# Micro.net
KiCad netlist of a schematic drawn in Altium Designer
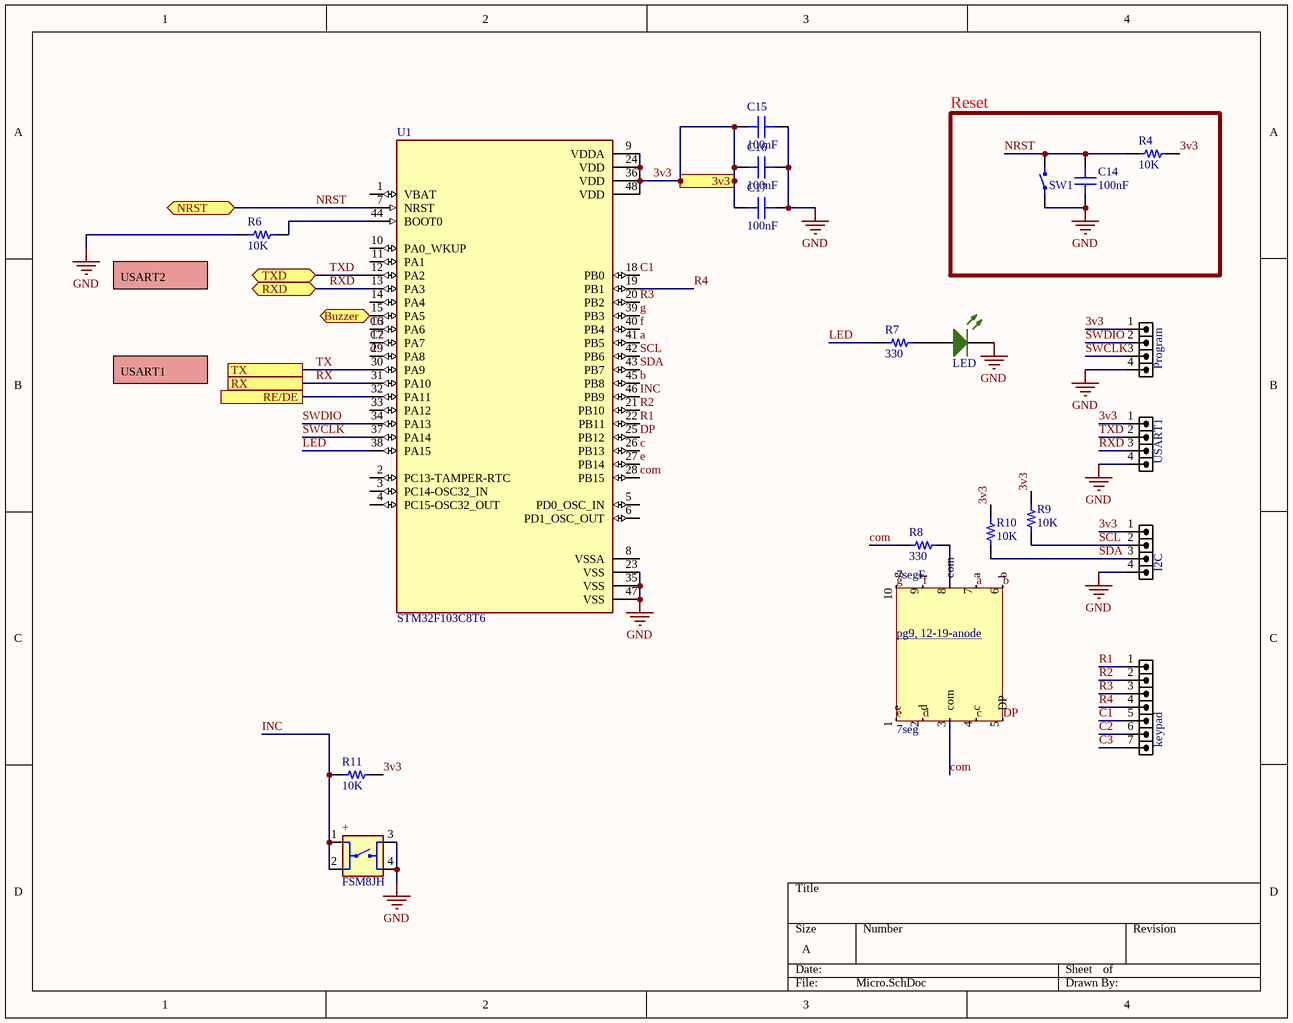
[diagram p0: Micro.SchDoc]

(export (version "E")
  (design (tool "Eeschema 10.0.6"))
  (components
    (comp (ref "+")
      (value "FSM8JH")
      (footprint "SW_FSM8JH")
      (description "Tactile Switch SPST-NO Top Actuated Through Hole")
      (fields (field (name "MF") "TE Connectivity"))
      (libsource (lib "FSM8JH") (part "FSM8JH"))
    )
    (comp (ref "7seg")
      (value "7seg")
      (footprint "PCBComponent_1")
      (description "file:///C:/Users/Tamana/Downloads/7SEG-12-19mm-GREEN-ANOD.pdf")
      (libsource (lib "7seg") (part "7seg"))
    )
    (comp (ref "C14")
      (value "100nF")
      (footprint "CAP 0805_2012")
      (description "SMT Capacitor")
      (libsource (lib "Capacitor") (part "Cap 0805"))
    )
    (comp (ref "C15")
      (value "100nF")
      (footprint "CAP 0805_2012")
      (description "SMT Capacitor")
      (libsource (lib "Capacitor") (part "Cap 0805"))
    )
    (comp (ref "C16")
      (value "100nF")
      (footprint "CAP 0805_2012")
      (description "SMT Capacitor")
      (libsource (lib "Capacitor") (part "Cap 0805"))
    )
    (comp (ref "C17")
      (value "100nF")
      (footprint "CAP 0805_2012")
      (description "SMT Capacitor")
      (libsource (lib "Capacitor") (part "Cap 0805"))
    )
    (comp (ref "I2C")
      (value "HDR1X4")
      (footprint "HDR_1X4")
      (description "CONN, HEADER, Male, pitch: 2.54mm, 4POS")
      (libsource (lib "Conn Header") (part "HDR_1X4"))
    )
    (comp (ref "keypad")
      (value "HDR1X7")
      (footprint "HDR_1X7")
      (description "CONN, HEADER, Male, pitch: 2.54mm, 7POS")
      (libsource (lib "Conn Header") (part "HDR_1X7"))
    )
    (comp (ref "LED")
      (value "LED SMD 0805 GREEN")
      (footprint "LED_0805_GREEN")
      (libsource (lib "Led") (part "LED SMD 0805 GREEN"))
    )
    (comp (ref "Program")
      (value "HDR1X4")
      (footprint "HDR_1X4")
      (description "CONN, HEADER, Male, pitch: 2.54mm, 4POS")
      (libsource (lib "Conn Header") (part "HDR_1X4"))
    )
    (comp (ref "R4")
      (value "10K")
      (footprint "RES 0805_2012")
      (description "SMT Resistor")
      (libsource (lib "Resistor") (part "Res 0805"))
    )
    (comp (ref "R6")
      (value "10K")
      (footprint "RES 0805_2012")
      (description "SMT Resistor")
      (libsource (lib "Resistor") (part "Res 0805"))
    )
    (comp (ref "R7")
      (value "330")
      (footprint "RES 0805_2012")
      (description "SMT Resistor")
      (libsource (lib "Resistor") (part "Res 0805"))
    )
    (comp (ref "R8")
      (value "330")
      (footprint "RES 0805_2012")
      (description "SMT Resistor")
      (libsource (lib "Resistor") (part "Res 0805"))
    )
    (comp (ref "R9")
      (value "10K")
      (footprint "RES 0805_2012")
      (description "SMT Resistor")
      (libsource (lib "Resistor") (part "Res 0805"))
    )
    (comp (ref "R10")
      (value "10K")
      (footprint "RES 0805_2012")
      (description "SMT Resistor")
      (libsource (lib "Resistor") (part "Res 0805"))
    )
    (comp (ref "R11")
      (value "10K")
      (footprint "RES 0805_2012")
      (description "SMT Resistor")
      (libsource (lib "Resistor") (part "Res 0805"))
    )
    (comp (ref "SW1")
      (value "Tactile 2PIN 6X3.5mm H4.57mm (SMD)")
      (footprint "SWPBS_SPST_6X3X5")
      (description "Tactile Switch SPST-NO Top Actuated Surface Mount")
      (fields (field (name "PARTNUMBER") "FSMSMTR-ND"))
      (libsource (lib "Switch") (part "Tactile 2PIN 6X3.5mm H4.57mm (SMD)"))
    )
    (comp (ref "U1")
      (value "STM32F103C8T6")
      (footprint "QFP50P900X900X160-48N")
      (description "ARM® Cortex®-M3 STM32F1 Microcontroller IC 32-Bit 72MHz 64KB (64K x 8) FLASH 48-LQFP (7x7)")
      (fields (field (name "MF") "STMicroelectronics"))
      (libsource (lib "STM32F103C8T6") (part "STM32F103C8T6"))
    )
    (comp (ref "USART1")
      (value "HDR1X4")
      (footprint "HDR_1X4")
      (description "CONN, HEADER, Male, pitch: 2.54mm, 4POS")
      (libsource (lib "Conn Header") (part "HDR_1X4"))
    )
  )
  (nets
    (net (code "1") (name "/3v3") (class "Default")
      (node (ref "C15") (pin "2") (pinfunction "2_2") (pintype "passive"))
      (node (ref "C16") (pin "2") (pinfunction "2_2") (pintype "passive"))
      (node (ref "C17") (pin "2") (pinfunction "2_2") (pintype "passive"))
      (node (ref "I2C") (pin "1") (pinfunction "1_1") (pintype "passive"))
      (node (ref "Program") (pin "1") (pinfunction "1_1") (pintype "passive"))
      (node (ref "R10") (pin "2") (pinfunction "2_2") (pintype "passive"))
      (node (ref "R11") (pin "2") (pinfunction "2_2") (pintype "passive"))
      (node (ref "R4") (pin "2") (pinfunction "2_2") (pintype "passive"))
      (node (ref "R9") (pin "2") (pinfunction "2_2") (pintype "passive"))
      (node (ref "U1") (pin "24") (pinfunction "VDD_24") (pintype "power_in"))
      (node (ref "U1") (pin "36") (pinfunction "VDD_36") (pintype "power_in"))
      (node (ref "U1") (pin "48") (pinfunction "VDD_48") (pintype "power_in"))
      (node (ref "U1") (pin "9") (pinfunction "VDDA_9") (pintype "power_in"))
      (node (ref "USART1") (pin "1") (pinfunction "1_1") (pintype "passive"))
    )
    (net (code "2") (name "/Buzzer") (class "Default")
      (node (ref "U1") (pin "15") (pinfunction "PA5_15") (pintype "bidirectional"))
    )
    (net (code "3") (name "/C1") (class "Default")
      (node (ref "U1") (pin "18") (pinfunction "PB0_18") (pintype "bidirectional"))
      (node (ref "keypad") (pin "5") (pinfunction "5_5") (pintype "passive"))
    )
    (net (code "4") (name "/C2") (class "Default")
      (node (ref "U1") (pin "17") (pinfunction "PA7_17") (pintype "bidirectional"))
      (node (ref "keypad") (pin "6") (pinfunction "6_6") (pintype "passive"))
    )
    (net (code "5") (name "/C3") (class "Default")
      (node (ref "U1") (pin "16") (pinfunction "PA6_16") (pintype "bidirectional"))
      (node (ref "keypad") (pin "7") (pinfunction "7_7") (pintype "passive"))
    )
    (net (code "6") (name "/DP") (class "Default")
      (node (ref "7seg") (pin "5") (pinfunction "DP_5") (pintype "passive"))
      (node (ref "U1") (pin "25") (pinfunction "PB12_25") (pintype "bidirectional"))
    )
    (net (code "7") (name "/INC") (class "Default")
      (node (ref "+") (pin "1") (pinfunction "1_1") (pintype "passive"))
      (node (ref "+") (pin "2") (pinfunction "2_2") (pintype "passive"))
      (node (ref "R11") (pin "1") (pinfunction "1_1") (pintype "passive"))
      (node (ref "U1") (pin "46") (pinfunction "PB9_46") (pintype "bidirectional"))
    )
    (net (code "8") (name "/LED") (class "Default")
      (node (ref "R7") (pin "1") (pinfunction "1_1") (pintype "passive"))
      (node (ref "U1") (pin "38") (pinfunction "PA15_38") (pintype "bidirectional"))
    )
    (net (code "9") (name "/NRST") (class "Default")
      (node (ref "C14") (pin "2") (pinfunction "2_2") (pintype "passive"))
      (node (ref "R4") (pin "1") (pinfunction "1_1") (pintype "passive"))
      (node (ref "SW1") (pin "2") (pinfunction "2_2") (pintype "passive"))
      (node (ref "U1") (pin "7") (pinfunction "NRST_7") (pintype "input"))
    )
    (net (code "10") (name "/R1") (class "Default")
      (node (ref "U1") (pin "22") (pinfunction "PB11_22") (pintype "bidirectional"))
      (node (ref "keypad") (pin "1") (pinfunction "1_1") (pintype "passive"))
    )
    (net (code "11") (name "/R2") (class "Default")
      (node (ref "U1") (pin "21") (pinfunction "PB10_21") (pintype "bidirectional"))
      (node (ref "keypad") (pin "2") (pinfunction "2_2") (pintype "passive"))
    )
    (net (code "12") (name "/R3") (class "Default")
      (node (ref "U1") (pin "20") (pinfunction "PB2_20") (pintype "bidirectional"))
      (node (ref "keypad") (pin "3") (pinfunction "3_3") (pintype "passive"))
    )
    (net (code "13") (name "/R4") (class "Default")
      (node (ref "U1") (pin "19") (pinfunction "PB1_19") (pintype "bidirectional"))
      (node (ref "keypad") (pin "4") (pinfunction "4_4") (pintype "passive"))
    )
    (net (code "14") (name "/RE{slash}DE") (class "Default")
      (node (ref "U1") (pin "32") (pinfunction "PA11_32") (pintype "bidirectional"))
    )
    (net (code "15") (name "/RX") (class "Default")
      (node (ref "U1") (pin "31") (pinfunction "PA10_31") (pintype "bidirectional"))
    )
    (net (code "16") (name "/RXD") (class "Default")
      (node (ref "U1") (pin "13") (pinfunction "PA3_13") (pintype "bidirectional"))
      (node (ref "USART1") (pin "3") (pinfunction "3_3") (pintype "passive"))
    )
    (net (code "17") (name "/SCL") (class "Default")
      (node (ref "I2C") (pin "2") (pinfunction "2_2") (pintype "passive"))
      (node (ref "R9") (pin "1") (pinfunction "1_1") (pintype "passive"))
      (node (ref "U1") (pin "42") (pinfunction "PB6_42") (pintype "bidirectional"))
    )
    (net (code "18") (name "/SDA") (class "Default")
      (node (ref "I2C") (pin "3") (pinfunction "3_3") (pintype "passive"))
      (node (ref "R10") (pin "1") (pinfunction "1_1") (pintype "passive"))
      (node (ref "U1") (pin "43") (pinfunction "PB7_43") (pintype "bidirectional"))
    )
    (net (code "19") (name "/SWCLK") (class "Default")
      (node (ref "Program") (pin "3") (pinfunction "3_3") (pintype "passive"))
      (node (ref "U1") (pin "37") (pinfunction "PA14_37") (pintype "bidirectional"))
    )
    (net (code "20") (name "/SWDIO") (class "Default")
      (node (ref "Program") (pin "2") (pinfunction "2_2") (pintype "passive"))
      (node (ref "U1") (pin "34") (pinfunction "PA13_34") (pintype "bidirectional"))
    )
    (net (code "21") (name "/TX") (class "Default")
      (node (ref "U1") (pin "30") (pinfunction "PA9_30") (pintype "bidirectional"))
    )
    (net (code "22") (name "/TXD") (class "Default")
      (node (ref "U1") (pin "12") (pinfunction "PA2_12") (pintype "bidirectional"))
      (node (ref "USART1") (pin "2") (pinfunction "2_2") (pintype "passive"))
    )
    (net (code "23") (name "/a") (class "Default")
      (node (ref "7seg") (pin "7") (pinfunction "a_7") (pintype "passive"))
      (node (ref "U1") (pin "41") (pinfunction "PB5_41") (pintype "bidirectional"))
    )
    (net (code "24") (name "/b") (class "Default")
      (node (ref "7seg") (pin "6") (pinfunction "b_6") (pintype "passive"))
      (node (ref "U1") (pin "45") (pinfunction "PB8_45") (pintype "bidirectional"))
    )
    (net (code "25") (name "/c") (class "Default")
      (node (ref "7seg") (pin "4") (pinfunction "c_4") (pintype "passive"))
      (node (ref "U1") (pin "26") (pinfunction "PB13_26") (pintype "bidirectional"))
    )
    (net (code "26") (name "/com") (class "Default")
      (node (ref "7seg") (pin "3") (pinfunction "com_3") (pintype "passive"))
      (node (ref "R8") (pin "1") (pinfunction "1_1") (pintype "passive"))
      (node (ref "U1") (pin "28") (pinfunction "PB15_28") (pintype "bidirectional"))
    )
    (net (code "27") (name "/d") (class "Default")
      (node (ref "7seg") (pin "2") (pinfunction "d_2") (pintype "passive"))
      (node (ref "U1") (pin "29") (pinfunction "PA8_29") (pintype "bidirectional"))
    )
    (net (code "28") (name "/e") (class "Default")
      (node (ref "7seg") (pin "1") (pinfunction "e_1") (pintype "passive"))
      (node (ref "U1") (pin "27") (pinfunction "PB14_27") (pintype "bidirectional"))
    )
    (net (code "29") (name "/f") (class "Default")
      (node (ref "7seg") (pin "9") (pinfunction "f_9") (pintype "passive"))
      (node (ref "U1") (pin "40") (pinfunction "PB4_40") (pintype "bidirectional"))
    )
    (net (code "30") (name "/g") (class "Default")
      (node (ref "7seg") (pin "10") (pinfunction "g_10") (pintype "passive"))
      (node (ref "U1") (pin "39") (pinfunction "PB3_39") (pintype "bidirectional"))
    )
    (net (code "31") (name "GND") (class "Default")
      (node (ref "+") (pin "3") (pinfunction "3_3") (pintype "passive"))
      (node (ref "+") (pin "4") (pinfunction "4_4") (pintype "passive"))
      (node (ref "C14") (pin "1") (pinfunction "1_1") (pintype "passive"))
      (node (ref "C15") (pin "1") (pinfunction "1_1") (pintype "passive"))
      (node (ref "C16") (pin "1") (pinfunction "1_1") (pintype "passive"))
      (node (ref "C17") (pin "1") (pinfunction "1_1") (pintype "passive"))
      (node (ref "I2C") (pin "4") (pinfunction "4_4") (pintype "passive"))
      (node (ref "LED") (pin "2") (pinfunction "K_2") (pintype "passive"))
      (node (ref "Program") (pin "4") (pinfunction "4_4") (pintype "passive"))
      (node (ref "R6") (pin "1") (pinfunction "1_1") (pintype "passive"))
      (node (ref "SW1") (pin "1") (pinfunction "1_1") (pintype "passive"))
      (node (ref "U1") (pin "23") (pinfunction "VSS_23") (pintype "power_in"))
      (node (ref "U1") (pin "35") (pinfunction "VSS_35") (pintype "power_in"))
      (node (ref "U1") (pin "47") (pinfunction "VSS_47") (pintype "power_in"))
      (node (ref "USART1") (pin "4") (pinfunction "4_4") (pintype "passive"))
    )
    (net (code "32") (name "Net-(7segF-com-Pad8)") (class "Default")
      (node (ref "7seg") (pin "8") (pinfunction "com_8") (pintype "passive"))
      (node (ref "R8") (pin "2") (pinfunction "2_2") (pintype "passive"))
    )
    (net (code "33") (name "Net-(LED-A)") (class "Default")
      (node (ref "LED") (pin "1") (pinfunction "A_1") (pintype "passive"))
      (node (ref "R7") (pin "2") (pinfunction "2_2") (pintype "passive"))
    )
    (net (code "34") (name "Net-(U1-BOOT0)") (class "Default")
      (node (ref "R6") (pin "2") (pinfunction "2_2") (pintype "passive"))
      (node (ref "U1") (pin "44") (pinfunction "BOOT0_44") (pintype "input"))
    )
    (net (code "35") (name "unconnected-(U1-PA0_WKUP-Pad10)") (class "Default")
      (node (ref "U1") (pin "10") (pinfunction "PA0_WKUP_10") (pintype "bidirectional"))
    )
    (net (code "36") (name "unconnected-(U1-PA1-Pad11)") (class "Default")
      (node (ref "U1") (pin "11") (pinfunction "PA1_11") (pintype "bidirectional"))
    )
    (net (code "37") (name "unconnected-(U1-PA4-Pad14)") (class "Default")
      (node (ref "U1") (pin "14") (pinfunction "PA4_14") (pintype "bidirectional"))
    )
    (net (code "38") (name "unconnected-(U1-PA12-Pad33)") (class "Default")
      (node (ref "U1") (pin "33") (pinfunction "PA12_33") (pintype "bidirectional"))
    )
    (net (code "39") (name "unconnected-(U1-PC13-TAMPER-RTC-Pad2)") (class "Default")
      (node (ref "U1") (pin "2") (pinfunction "PC13-TAMPER-RTC_2") (pintype "bidirectional"))
    )
    (net (code "40") (name "unconnected-(U1-PC14-OSC32_IN-Pad3)") (class "Default")
      (node (ref "U1") (pin "3") (pinfunction "PC14-OSC32_IN_3") (pintype "bidirectional"))
    )
    (net (code "41") (name "unconnected-(U1-PC15-OSC32_OUT-Pad4)") (class "Default")
      (node (ref "U1") (pin "4") (pinfunction "PC15-OSC32_OUT_4") (pintype "bidirectional"))
    )
    (net (code "42") (name "unconnected-(U1-PD0_OSC_IN-Pad5)") (class "Default")
      (node (ref "U1") (pin "5") (pinfunction "PD0_OSC_IN_5") (pintype "bidirectional"))
    )
    (net (code "43") (name "unconnected-(U1-PD1_OSC_OUT-Pad6)") (class "Default")
      (node (ref "U1") (pin "6") (pinfunction "PD1_OSC_OUT_6") (pintype "bidirectional"))
    )
    (net (code "44") (name "unconnected-(U1-VBAT-Pad1)") (class "Default")
      (node (ref "U1") (pin "1") (pinfunction "VBAT_1") (pintype "bidirectional"))
    )
    (net (code "45") (name "unconnected-(U1-VSSA-Pad8)") (class "Default")
      (node (ref "U1") (pin "8") (pinfunction "VSSA_8") (pintype "power_in"))
    )
  )
)
